# Sheet1.net
KiCad netlist of a schematic drawn in Altium Designer
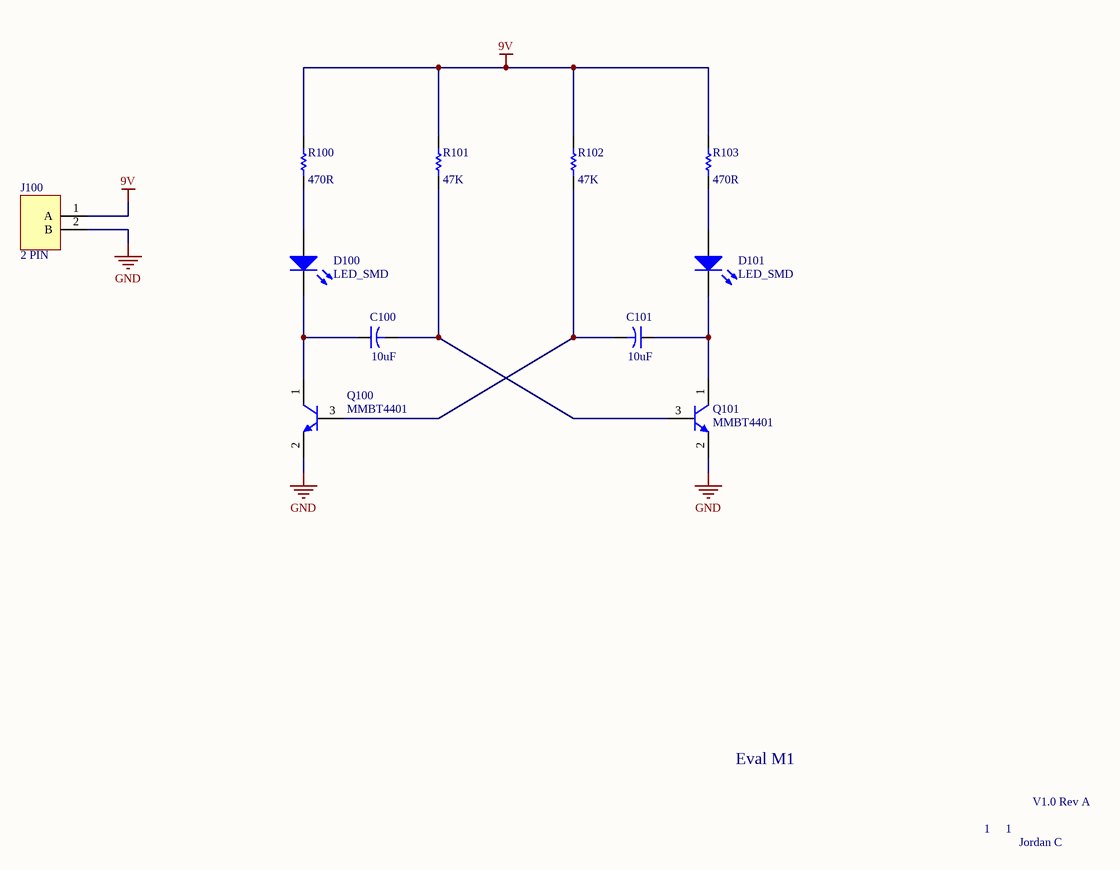
[diagram p0: Sheet1.SchDoc]

(export (version "E")
  (design (tool "Eeschema 10.0.6"))
  (components
    (comp (ref "C100")
      (value "10uF")
      (footprint "CAPR5-4X5")
      (description "Capacitor")
      (fields (field (name "Comment") "Cap2"))
      (libsource (lib "Schlib1") (part "Cap2"))
    )
    (comp (ref "C101")
      (value "10uF")
      (footprint "CAPR5-4X5")
      (description "Capacitor")
      (fields (field (name "Comment") "Cap2"))
      (libsource (lib "Schlib1") (part "Cap2"))
    )
    (comp (ref "D100")
      (value "LED_SMD")
      (footprint "0603_LED")
      (description "LED RED CLEAR 0603 SMD")
      (fields
        (field (name "DIGIKEY PART NUMBER") "160-1447-1-ND")
        (field (name "MANUFACTURER PART NUMBER") "LTST-C191KRKT")
      )
      (libsource (lib "Schlib1") (part "LED_SMD"))
    )
    (comp (ref "D101")
      (value "LED_SMD")
      (footprint "0603_LED")
      (description "LED RED CLEAR 0603 SMD")
      (fields
        (field (name "DIGIKEY PART NUMBER") "160-1447-1-ND")
        (field (name "MANUFACTURER PART NUMBER") "LTST-C191KRKT")
      )
      (libsource (lib "Schlib1") (part "LED_SMD"))
    )
    (comp (ref "J100")
      (value "2 PIN")
      (footprint "Header 2_PIN")
      (libsource (lib "Schlib1") (part "Connector_2Pin"))
    )
    (comp (ref "Q100")
      (value "MMBT4401")
      (footprint "SOT23_N")
      (description "NPN Bipolar Transistor")
      (fields
        (field (name "DIGIKEY PART NUMBER") "MMBT4401LT1GOSCT-ND")
        (field (name "MANUFACTURER") "ON Semiconductor")
      )
      (libsource (lib "Schlib1") (part "NPN"))
    )
    (comp (ref "Q101")
      (value "MMBT4401")
      (footprint "SOT23_N")
      (description "NPN Bipolar Transistor")
      (fields
        (field (name "DIGIKEY PART NUMBER") "MMBT4401LT1GOSCT-ND")
        (field (name "MANUFACTURER") "ON Semiconductor")
      )
      (libsource (lib "Schlib1") (part "NPN"))
    )
    (comp (ref "R100")
      (value "470R")
      (footprint "R0603")
      (description "Resistor")
      (fields (field (name "Comment") "Res1"))
      (libsource (lib "Schlib1") (part "Res1"))
    )
    (comp (ref "R101")
      (value "47K")
      (footprint "R0603")
      (description "Resistor")
      (fields (field (name "Comment") "Res1"))
      (libsource (lib "Schlib1") (part "Res1"))
    )
    (comp (ref "R102")
      (value "47K")
      (footprint "R0603")
      (description "Resistor")
      (fields (field (name "Comment") "Res1"))
      (libsource (lib "Schlib1") (part "Res1"))
    )
    (comp (ref "R103")
      (value "470R")
      (footprint "R0603")
      (description "Resistor")
      (fields (field (name "Comment") "Res1"))
      (libsource (lib "Schlib1") (part "Res1"))
    )
  )
  (nets
    (net (code "1") (name "9V") (class "Default")
      (node (ref "J100") (pin "1") (pinfunction "A_1") (pintype "passive"))
      (node (ref "R100") (pin "1") (pinfunction "1_1") (pintype "passive"))
      (node (ref "R101") (pin "1") (pinfunction "1_1") (pintype "passive"))
      (node (ref "R102") (pin "1") (pinfunction "1_1") (pintype "passive"))
      (node (ref "R103") (pin "1") (pinfunction "1_1") (pintype "passive"))
    )
    (net (code "2") (name "GND") (class "Default")
      (node (ref "J100") (pin "2") (pinfunction "B_2") (pintype "passive"))
      (node (ref "Q100") (pin "2") (pinfunction "E_2") (pintype "passive"))
      (node (ref "Q101") (pin "2") (pinfunction "E_2") (pintype "passive"))
    )
    (net (code "3") (name "Net-(D100-A)") (class "Default")
      (node (ref "D100") (pin "1") (pinfunction "A_1") (pintype "passive"))
      (node (ref "R100") (pin "2") (pinfunction "2_2") (pintype "passive"))
    )
    (net (code "4") (name "Net-(D100-K)") (class "Default")
      (node (ref "C100") (pin "1") (pinfunction "1_1") (pintype "passive"))
      (node (ref "D100") (pin "2") (pinfunction "K_2") (pintype "passive"))
      (node (ref "Q100") (pin "1") (pinfunction "C_1") (pintype "passive"))
    )
    (net (code "5") (name "Net-(D101-A)") (class "Default")
      (node (ref "D101") (pin "1") (pinfunction "A_1") (pintype "passive"))
      (node (ref "R103") (pin "2") (pinfunction "2_2") (pintype "passive"))
    )
    (net (code "6") (name "Net-(D101-K)") (class "Default")
      (node (ref "C101") (pin "1") (pinfunction "1_1") (pintype "passive"))
      (node (ref "D101") (pin "2") (pinfunction "K_2") (pintype "passive"))
      (node (ref "Q101") (pin "1") (pinfunction "C_1") (pintype "passive"))
    )
    (net (code "7") (name "Net-(Q100-B)") (class "Default")
      (node (ref "C101") (pin "2") (pinfunction "2_2") (pintype "passive"))
      (node (ref "Q100") (pin "3") (pinfunction "B_3") (pintype "passive"))
      (node (ref "R102") (pin "2") (pinfunction "2_2") (pintype "passive"))
    )
    (net (code "8") (name "Net-(Q101-B)") (class "Default")
      (node (ref "C100") (pin "2") (pinfunction "2_2") (pintype "passive"))
      (node (ref "Q101") (pin "3") (pinfunction "B_3") (pintype "passive"))
      (node (ref "R101") (pin "2") (pinfunction "2_2") (pintype "passive"))
    )
  )
)
